# Hypertronicsboard.net
KiCad netlist of a schematic drawn in EAGLE
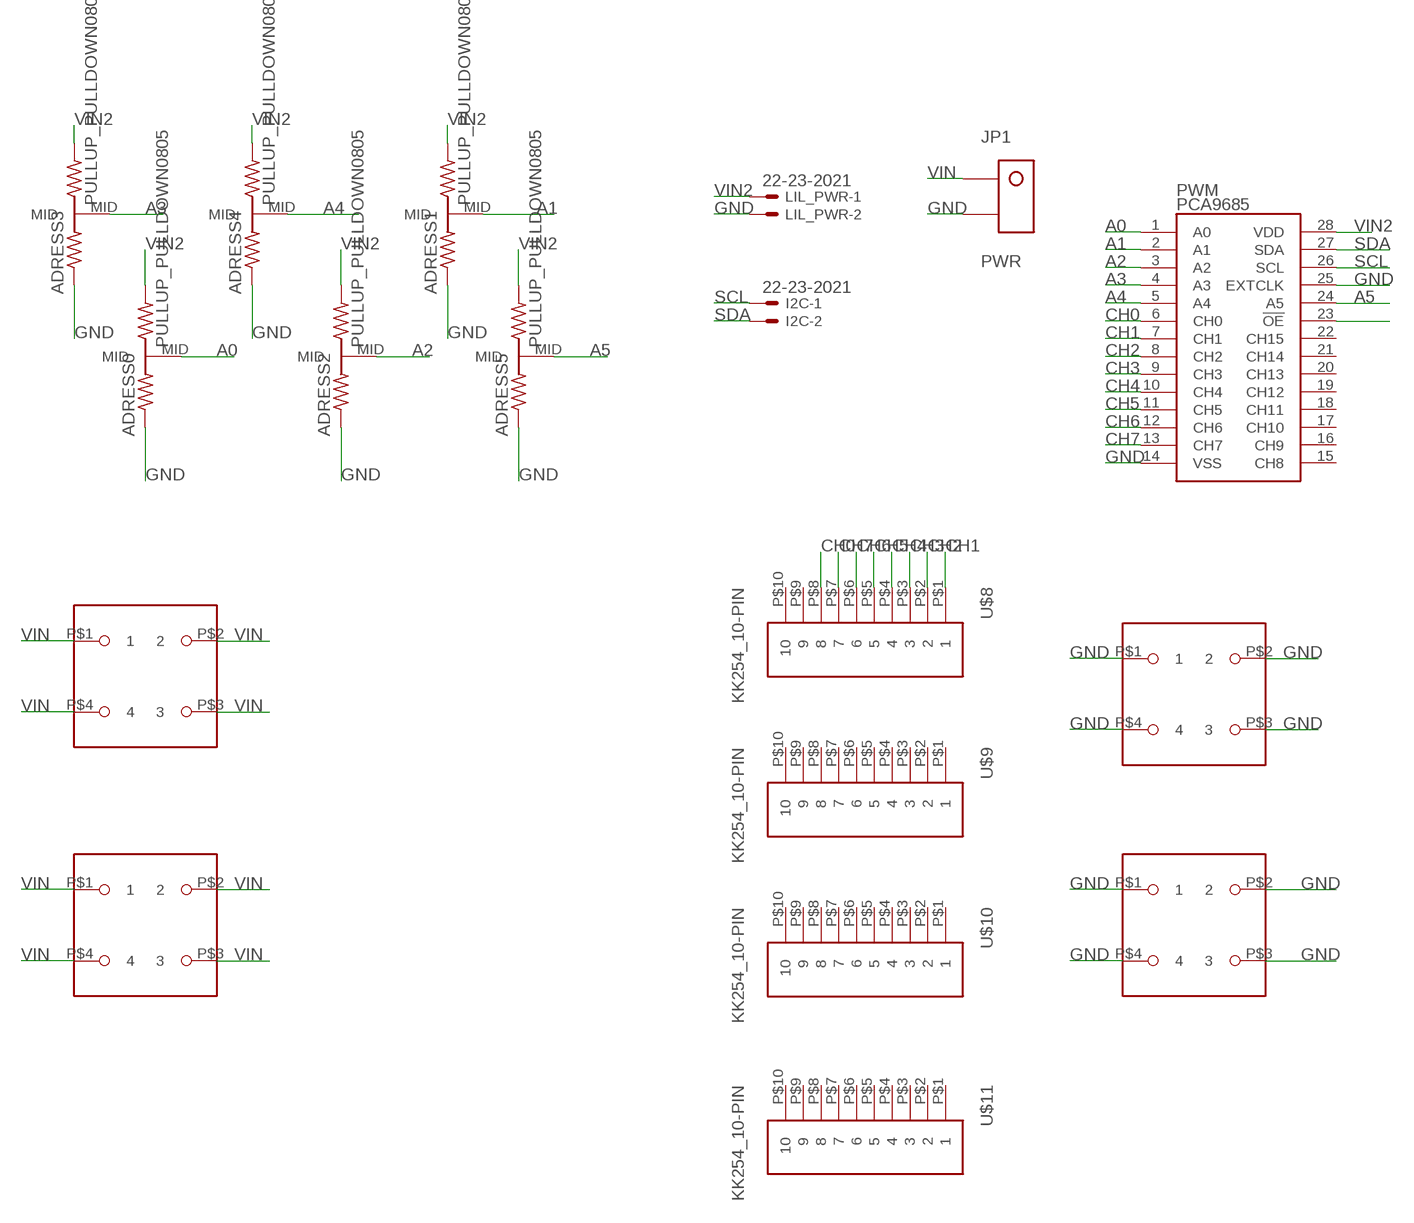
[diagram p0: schematic, sheet 1]

(export (version "E")
  (design (tool "Eeschema 10.0.6"))
  (components
    (comp (ref "ADRESS0")
      (value "PULLUP_PULLDOWN0805")
      (footprint "eagle-import:PULLUP_PULLDOWN_0805")
      (libsource (lib "eagle-import") (part "PULLUP_PULLDOWN0805"))
    )
    (comp (ref "ADRESS1")
      (value "PULLUP_PULLDOWN0805")
      (footprint "eagle-import:PULLUP_PULLDOWN_0805")
      (libsource (lib "eagle-import") (part "PULLUP_PULLDOWN0805"))
    )
    (comp (ref "ADRESS2")
      (value "PULLUP_PULLDOWN0805")
      (footprint "eagle-import:PULLUP_PULLDOWN_0805")
      (libsource (lib "eagle-import") (part "PULLUP_PULLDOWN0805"))
    )
    (comp (ref "ADRESS3")
      (value "PULLUP_PULLDOWN0805")
      (footprint "eagle-import:PULLUP_PULLDOWN_0805")
      (libsource (lib "eagle-import") (part "PULLUP_PULLDOWN0805"))
    )
    (comp (ref "ADRESS4")
      (value "PULLUP_PULLDOWN0805")
      (footprint "eagle-import:PULLUP_PULLDOWN_0805")
      (libsource (lib "eagle-import") (part "PULLUP_PULLDOWN0805"))
    )
    (comp (ref "ADRESS5")
      (value "PULLUP_PULLDOWN0805")
      (footprint "eagle-import:PULLUP_PULLDOWN_0805")
      (libsource (lib "eagle-import") (part "PULLUP_PULLDOWN0805"))
    )
    (comp (ref "I2C")
      (value "22-23-2021")
      (footprint "eagle-import:22-23-2021")
      (fields (field (name "MF") "MOLEX"))
      (libsource (lib "eagle-import") (part "22-23-2021"))
    )
    (comp (ref "JP1")
      (value "PWR")
      (footprint "eagle-import:SUPERSABRE_2CIRCUIT")
      (libsource (lib "eagle-import") (part "2_SUPERSABRE"))
    )
    (comp (ref "LIL_PWR")
      (value "22-23-2021")
      (footprint "eagle-import:22-23-2021")
      (fields (field (name "MF") "MOLEX"))
      (libsource (lib "eagle-import") (part "22-23-2021"))
    )
    (comp (ref "PWM")
      (value "PCA9685")
      (footprint "eagle-import:TSSOP-28_4MM")
      (libsource (lib "eagle-import") (part "PCA9685"))
    )
    (comp (ref "U$1")
      (value "BCS-106-L-D-PE-BE")
      (footprint "eagle-import:4-PIN-BIGPOWER")
      (libsource (lib "eagle-import") (part "BCS-106-L-D-PE-BE"))
    )
    (comp (ref "U$2")
      (value "BCS-106-L-D-PE-BE")
      (footprint "eagle-import:4-PIN-BIGPOWER")
      (libsource (lib "eagle-import") (part "BCS-106-L-D-PE-BE"))
    )
    (comp (ref "U$3")
      (value "BCS-106-L-D-PE-BE")
      (footprint "eagle-import:4-PIN-BIGPOWER")
      (libsource (lib "eagle-import") (part "BCS-106-L-D-PE-BE"))
    )
    (comp (ref "U$4")
      (value "BCS-106-L-D-PE-BE")
      (footprint "eagle-import:4-PIN-BIGPOWER")
      (libsource (lib "eagle-import") (part "BCS-106-L-D-PE-BE"))
    )
    (comp (ref "U$8")
      (value "KK254_10-PIN")
      (footprint "eagle-import:KK254_10-PIN")
      (libsource (lib "eagle-import") (part "KK254_10-PIN"))
    )
    (comp (ref "U$9")
      (value "KK254_10-PIN")
      (footprint "eagle-import:KK254_10-PIN")
      (libsource (lib "eagle-import") (part "KK254_10-PIN"))
    )
    (comp (ref "U$10")
      (value "KK254_10-PIN")
      (footprint "eagle-import:KK254_10-PIN")
      (libsource (lib "eagle-import") (part "KK254_10-PIN"))
    )
    (comp (ref "U$11")
      (value "KK254_10-PIN")
      (footprint "eagle-import:KK254_10-PIN")
      (libsource (lib "eagle-import") (part "KK254_10-PIN"))
    )
  )
  (nets
    (net (code "1") (name "/A0") (class "Default")
      (node (ref "ADRESS0") (pin "MID") (pinfunction "MID_MID") (pintype "bidirectional"))
      (node (ref "PWM") (pin "1") (pinfunction "A0_1") (pintype "bidirectional"))
    )
    (net (code "2") (name "/A1") (class "Default")
      (node (ref "ADRESS1") (pin "MID") (pinfunction "MID_MID") (pintype "bidirectional"))
      (node (ref "PWM") (pin "2") (pinfunction "A1_2") (pintype "bidirectional"))
    )
    (net (code "3") (name "/A2") (class "Default")
      (node (ref "ADRESS2") (pin "MID") (pinfunction "MID_MID") (pintype "bidirectional"))
      (node (ref "PWM") (pin "3") (pinfunction "A2_3") (pintype "bidirectional"))
    )
    (net (code "4") (name "/A3") (class "Default")
      (node (ref "ADRESS3") (pin "MID") (pinfunction "MID_MID") (pintype "bidirectional"))
      (node (ref "PWM") (pin "4") (pinfunction "A3_4") (pintype "bidirectional"))
    )
    (net (code "5") (name "/A4") (class "Default")
      (node (ref "ADRESS4") (pin "MID") (pinfunction "MID_MID") (pintype "bidirectional"))
      (node (ref "PWM") (pin "5") (pinfunction "A4_5") (pintype "bidirectional"))
    )
    (net (code "6") (name "/A5") (class "Default")
      (node (ref "ADRESS5") (pin "MID") (pinfunction "MID_MID") (pintype "bidirectional"))
      (node (ref "PWM") (pin "24") (pinfunction "A5_24") (pintype "bidirectional"))
    )
    (net (code "7") (name "/CH0") (class "Default")
      (node (ref "PWM") (pin "6") (pinfunction "CH0_6") (pintype "bidirectional"))
      (node (ref "U$8") (pin "P$8") (pinfunction "8_P$8") (pintype "bidirectional"))
    )
    (net (code "8") (name "/CH1") (class "Default")
      (node (ref "PWM") (pin "7") (pinfunction "CH1_7") (pintype "bidirectional"))
      (node (ref "U$8") (pin "P$1") (pinfunction "1_P$1") (pintype "bidirectional"))
    )
    (net (code "9") (name "/CH2") (class "Default")
      (node (ref "PWM") (pin "8") (pinfunction "CH2_8") (pintype "bidirectional"))
      (node (ref "U$8") (pin "P$2") (pinfunction "2_P$2") (pintype "bidirectional"))
    )
    (net (code "10") (name "/CH3") (class "Default")
      (node (ref "PWM") (pin "9") (pinfunction "CH3_9") (pintype "bidirectional"))
      (node (ref "U$8") (pin "P$3") (pinfunction "3_P$3") (pintype "bidirectional"))
    )
    (net (code "11") (name "/CH4") (class "Default")
      (node (ref "PWM") (pin "10") (pinfunction "CH4_10") (pintype "bidirectional"))
      (node (ref "U$8") (pin "P$4") (pinfunction "4_P$4") (pintype "bidirectional"))
    )
    (net (code "12") (name "/CH5") (class "Default")
      (node (ref "PWM") (pin "11") (pinfunction "CH5_11") (pintype "bidirectional"))
      (node (ref "U$8") (pin "P$5") (pinfunction "5_P$5") (pintype "bidirectional"))
    )
    (net (code "13") (name "/CH6") (class "Default")
      (node (ref "PWM") (pin "12") (pinfunction "CH6_12") (pintype "bidirectional"))
      (node (ref "U$8") (pin "P$6") (pinfunction "6_P$6") (pintype "bidirectional"))
    )
    (net (code "14") (name "/CH7") (class "Default")
      (node (ref "PWM") (pin "13") (pinfunction "CH7_13") (pintype "bidirectional"))
      (node (ref "U$8") (pin "P$7") (pinfunction "7_P$7") (pintype "bidirectional"))
    )
    (net (code "15") (name "/GND") (class "Default")
      (node (ref "ADRESS0") (pin "GND") (pinfunction "GND_GND") (pintype "passive"))
      (node (ref "ADRESS1") (pin "GND") (pinfunction "GND_GND") (pintype "passive"))
      (node (ref "ADRESS2") (pin "GND") (pinfunction "GND_GND") (pintype "passive"))
      (node (ref "ADRESS3") (pin "GND") (pinfunction "GND_GND") (pintype "passive"))
      (node (ref "ADRESS4") (pin "GND") (pinfunction "GND_GND") (pintype "passive"))
      (node (ref "ADRESS5") (pin "GND") (pinfunction "GND_GND") (pintype "passive"))
      (node (ref "JP1") (pin "P$2") (pinfunction "P$2_P$2") (pintype "bidirectional"))
      (node (ref "LIL_PWR") (pin "2") (pinfunction "S_2") (pintype "passive"))
      (node (ref "PWM") (pin "14") (pinfunction "VSS_14") (pintype "bidirectional"))
      (node (ref "PWM") (pin "25") (pinfunction "EXTCLK_25") (pintype "bidirectional"))
      (node (ref "U$3") (pin "P$1") (pinfunction "1_P$1") (pintype "bidirectional"))
      (node (ref "U$3") (pin "P$2") (pinfunction "2_P$2") (pintype "bidirectional"))
      (node (ref "U$3") (pin "P$3") (pinfunction "3_P$3") (pintype "bidirectional"))
      (node (ref "U$3") (pin "P$4") (pinfunction "4_P$4") (pintype "bidirectional"))
      (node (ref "U$4") (pin "P$1") (pinfunction "1_P$1") (pintype "bidirectional"))
      (node (ref "U$4") (pin "P$2") (pinfunction "2_P$2") (pintype "bidirectional"))
      (node (ref "U$4") (pin "P$3") (pinfunction "3_P$3") (pintype "bidirectional"))
      (node (ref "U$4") (pin "P$4") (pinfunction "4_P$4") (pintype "bidirectional"))
    )
    (net (code "16") (name "/SCL") (class "Default")
      (node (ref "I2C") (pin "1") (pinfunction "S_1") (pintype "passive"))
      (node (ref "PWM") (pin "26") (pinfunction "SCL_26") (pintype "bidirectional"))
    )
    (net (code "17") (name "/SDA") (class "Default")
      (node (ref "I2C") (pin "2") (pinfunction "S_2") (pintype "passive"))
      (node (ref "PWM") (pin "27") (pinfunction "SDA_27") (pintype "bidirectional"))
    )
    (net (code "18") (name "/VIN") (class "Default")
      (node (ref "JP1") (pin "P$1") (pinfunction "P$1_P$1") (pintype "bidirectional"))
      (node (ref "U$1") (pin "P$1") (pinfunction "1_P$1") (pintype "bidirectional"))
      (node (ref "U$1") (pin "P$2") (pinfunction "2_P$2") (pintype "bidirectional"))
      (node (ref "U$1") (pin "P$3") (pinfunction "3_P$3") (pintype "bidirectional"))
      (node (ref "U$1") (pin "P$4") (pinfunction "4_P$4") (pintype "bidirectional"))
      (node (ref "U$2") (pin "P$1") (pinfunction "1_P$1") (pintype "bidirectional"))
      (node (ref "U$2") (pin "P$2") (pinfunction "2_P$2") (pintype "bidirectional"))
      (node (ref "U$2") (pin "P$3") (pinfunction "3_P$3") (pintype "bidirectional"))
      (node (ref "U$2") (pin "P$4") (pinfunction "4_P$4") (pintype "bidirectional"))
    )
    (net (code "19") (name "/VIN2") (class "Default")
      (node (ref "ADRESS0") (pin "VCC") (pinfunction "PWR_VCC") (pintype "passive"))
      (node (ref "ADRESS1") (pin "VCC") (pinfunction "PWR_VCC") (pintype "passive"))
      (node (ref "ADRESS2") (pin "VCC") (pinfunction "PWR_VCC") (pintype "passive"))
      (node (ref "ADRESS3") (pin "VCC") (pinfunction "PWR_VCC") (pintype "passive"))
      (node (ref "ADRESS4") (pin "VCC") (pinfunction "PWR_VCC") (pintype "passive"))
      (node (ref "ADRESS5") (pin "VCC") (pinfunction "PWR_VCC") (pintype "passive"))
      (node (ref "LIL_PWR") (pin "1") (pinfunction "S_1") (pintype "passive"))
      (node (ref "PWM") (pin "28") (pinfunction "VDD_28") (pintype "bidirectional"))
    )
    (net (code "20") (name "unconnected-(PWM-CH8-Pad15)") (class "Default")
      (node (ref "PWM") (pin "15") (pinfunction "CH8_15") (pintype "bidirectional"))
    )
    (net (code "21") (name "unconnected-(PWM-CH9-Pad16)") (class "Default")
      (node (ref "PWM") (pin "16") (pinfunction "CH9_16") (pintype "bidirectional"))
    )
    (net (code "22") (name "unconnected-(PWM-CH10-Pad17)") (class "Default")
      (node (ref "PWM") (pin "17") (pinfunction "CH10_17") (pintype "bidirectional"))
    )
    (net (code "23") (name "unconnected-(PWM-CH11-Pad18)") (class "Default")
      (node (ref "PWM") (pin "18") (pinfunction "CH11_18") (pintype "bidirectional"))
    )
    (net (code "24") (name "unconnected-(PWM-CH12-Pad19)") (class "Default")
      (node (ref "PWM") (pin "19") (pinfunction "CH12_19") (pintype "bidirectional"))
    )
    (net (code "25") (name "unconnected-(PWM-CH13-Pad20)") (class "Default")
      (node (ref "PWM") (pin "20") (pinfunction "CH13_20") (pintype "bidirectional"))
    )
    (net (code "26") (name "unconnected-(PWM-CH14-Pad21)") (class "Default")
      (node (ref "PWM") (pin "21") (pinfunction "CH14_21") (pintype "bidirectional"))
    )
    (net (code "27") (name "unconnected-(PWM-CH15-Pad22)") (class "Default")
      (node (ref "PWM") (pin "22") (pinfunction "CH15_22") (pintype "bidirectional"))
    )
    (net (code "28") (name "unconnected-(PWM-~{OE}-Pad23)") (class "Default")
      (node (ref "PWM") (pin "23") (pinfunction "~{OE}_23") (pintype "bidirectional"))
    )
    (net (code "29") (name "unconnected-(U$8-9-PadP$9)") (class "Default")
      (node (ref "U$8") (pin "P$9") (pinfunction "9_P$9") (pintype "bidirectional"))
    )
    (net (code "30") (name "unconnected-(U$8-10-PadP$10)") (class "Default")
      (node (ref "U$8") (pin "P$10") (pinfunction "10_P$10") (pintype "bidirectional"))
    )
    (net (code "31") (name "unconnected-(U$9-1-PadP$1)") (class "Default")
      (node (ref "U$9") (pin "P$1") (pinfunction "1_P$1") (pintype "bidirectional"))
    )
    (net (code "32") (name "unconnected-(U$9-2-PadP$2)") (class "Default")
      (node (ref "U$9") (pin "P$2") (pinfunction "2_P$2") (pintype "bidirectional"))
    )
    (net (code "33") (name "unconnected-(U$9-3-PadP$3)") (class "Default")
      (node (ref "U$9") (pin "P$3") (pinfunction "3_P$3") (pintype "bidirectional"))
    )
    (net (code "34") (name "unconnected-(U$9-4-PadP$4)") (class "Default")
      (node (ref "U$9") (pin "P$4") (pinfunction "4_P$4") (pintype "bidirectional"))
    )
    (net (code "35") (name "unconnected-(U$9-5-PadP$5)") (class "Default")
      (node (ref "U$9") (pin "P$5") (pinfunction "5_P$5") (pintype "bidirectional"))
    )
    (net (code "36") (name "unconnected-(U$9-6-PadP$6)") (class "Default")
      (node (ref "U$9") (pin "P$6") (pinfunction "6_P$6") (pintype "bidirectional"))
    )
    (net (code "37") (name "unconnected-(U$9-7-PadP$7)") (class "Default")
      (node (ref "U$9") (pin "P$7") (pinfunction "7_P$7") (pintype "bidirectional"))
    )
    (net (code "38") (name "unconnected-(U$9-8-PadP$8)") (class "Default")
      (node (ref "U$9") (pin "P$8") (pinfunction "8_P$8") (pintype "bidirectional"))
    )
    (net (code "39") (name "unconnected-(U$9-9-PadP$9)") (class "Default")
      (node (ref "U$9") (pin "P$9") (pinfunction "9_P$9") (pintype "bidirectional"))
    )
    (net (code "40") (name "unconnected-(U$9-10-PadP$10)") (class "Default")
      (node (ref "U$9") (pin "P$10") (pinfunction "10_P$10") (pintype "bidirectional"))
    )
    (net (code "41") (name "unconnected-(U$10-1-PadP$1)") (class "Default")
      (node (ref "U$10") (pin "P$1") (pinfunction "1_P$1") (pintype "bidirectional"))
    )
    (net (code "42") (name "unconnected-(U$10-2-PadP$2)") (class "Default")
      (node (ref "U$10") (pin "P$2") (pinfunction "2_P$2") (pintype "bidirectional"))
    )
    (net (code "43") (name "unconnected-(U$10-3-PadP$3)") (class "Default")
      (node (ref "U$10") (pin "P$3") (pinfunction "3_P$3") (pintype "bidirectional"))
    )
    (net (code "44") (name "unconnected-(U$10-4-PadP$4)") (class "Default")
      (node (ref "U$10") (pin "P$4") (pinfunction "4_P$4") (pintype "bidirectional"))
    )
    (net (code "45") (name "unconnected-(U$10-5-PadP$5)") (class "Default")
      (node (ref "U$10") (pin "P$5") (pinfunction "5_P$5") (pintype "bidirectional"))
    )
    (net (code "46") (name "unconnected-(U$10-6-PadP$6)") (class "Default")
      (node (ref "U$10") (pin "P$6") (pinfunction "6_P$6") (pintype "bidirectional"))
    )
    (net (code "47") (name "unconnected-(U$10-7-PadP$7)") (class "Default")
      (node (ref "U$10") (pin "P$7") (pinfunction "7_P$7") (pintype "bidirectional"))
    )
    (net (code "48") (name "unconnected-(U$10-8-PadP$8)") (class "Default")
      (node (ref "U$10") (pin "P$8") (pinfunction "8_P$8") (pintype "bidirectional"))
    )
    (net (code "49") (name "unconnected-(U$10-9-PadP$9)") (class "Default")
      (node (ref "U$10") (pin "P$9") (pinfunction "9_P$9") (pintype "bidirectional"))
    )
    (net (code "50") (name "unconnected-(U$10-10-PadP$10)") (class "Default")
      (node (ref "U$10") (pin "P$10") (pinfunction "10_P$10") (pintype "bidirectional"))
    )
    (net (code "51") (name "unconnected-(U$11-1-PadP$1)") (class "Default")
      (node (ref "U$11") (pin "P$1") (pinfunction "1_P$1") (pintype "bidirectional"))
    )
    (net (code "52") (name "unconnected-(U$11-2-PadP$2)") (class "Default")
      (node (ref "U$11") (pin "P$2") (pinfunction "2_P$2") (pintype "bidirectional"))
    )
    (net (code "53") (name "unconnected-(U$11-3-PadP$3)") (class "Default")
      (node (ref "U$11") (pin "P$3") (pinfunction "3_P$3") (pintype "bidirectional"))
    )
    (net (code "54") (name "unconnected-(U$11-4-PadP$4)") (class "Default")
      (node (ref "U$11") (pin "P$4") (pinfunction "4_P$4") (pintype "bidirectional"))
    )
    (net (code "55") (name "unconnected-(U$11-5-PadP$5)") (class "Default")
      (node (ref "U$11") (pin "P$5") (pinfunction "5_P$5") (pintype "bidirectional"))
    )
    (net (code "56") (name "unconnected-(U$11-6-PadP$6)") (class "Default")
      (node (ref "U$11") (pin "P$6") (pinfunction "6_P$6") (pintype "bidirectional"))
    )
    (net (code "57") (name "unconnected-(U$11-7-PadP$7)") (class "Default")
      (node (ref "U$11") (pin "P$7") (pinfunction "7_P$7") (pintype "bidirectional"))
    )
    (net (code "58") (name "unconnected-(U$11-8-PadP$8)") (class "Default")
      (node (ref "U$11") (pin "P$8") (pinfunction "8_P$8") (pintype "bidirectional"))
    )
    (net (code "59") (name "unconnected-(U$11-9-PadP$9)") (class "Default")
      (node (ref "U$11") (pin "P$9") (pinfunction "9_P$9") (pintype "bidirectional"))
    )
    (net (code "60") (name "unconnected-(U$11-10-PadP$10)") (class "Default")
      (node (ref "U$11") (pin "P$10") (pinfunction "10_P$10") (pintype "bidirectional"))
    )
  )
)
